# 12VSupply.net
KiCad netlist of a schematic drawn in Altium Designer
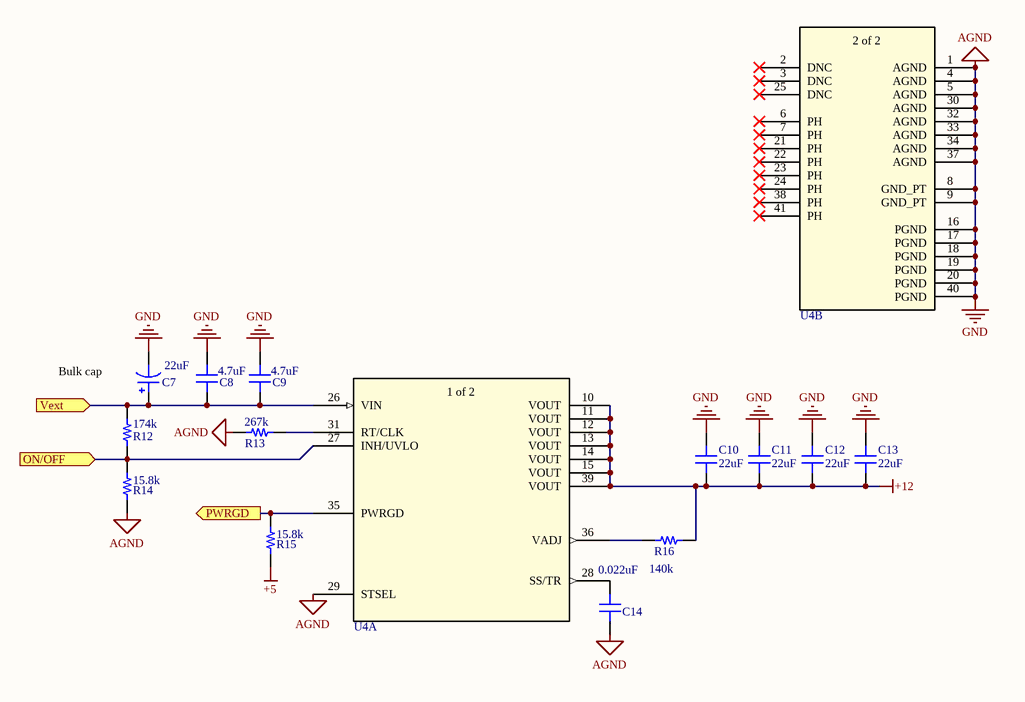
[diagram p0: 12VSupply.SchDoc]

(export (version "E")
  (design (tool "Eeschema 10.0.6"))
  (components
    (comp (ref "C7")
      (value "22uF")
      (footprint "CAP AL TH D8 L3.5 H11.5")
      (description "CAP ALUM 22UF 20% 100V RADIAL")
      (fields
        (field (name "PART NUMBER") "EEU-FC2A220")
        (field (name "MANUFACTURER") "Panasonic Electronic Components")
      )
      (libsource (lib "Celestial Library Database") (part "Polarised Capacitor"))
    )
    (comp (ref "C8")
      (value "4.7uF")
      (footprint "CAP 1206/3216 - 1.0MM")
      (description "CAP CER 4.7UF 50V X5R 1206")
      (fields
        (field (name "PART NUMBER") "C3216X5R1H475K085AB")
        (field (name "MANUFACTURER") "TDK Corporation")
      )
      (libsource (lib "Celestial Library Database") (part "Capacitor"))
    )
    (comp (ref "C9")
      (value "4.7uF")
      (footprint "CAP 1206/3216 - 1.0MM")
      (description "CAP CER 4.7UF 50V X5R 1206")
      (fields
        (field (name "PART NUMBER") "C3216X5R1H475K085AB")
        (field (name "MANUFACTURER") "TDK Corporation")
      )
      (libsource (lib "Celestial Library Database") (part "Capacitor"))
    )
    (comp (ref "C10")
      (value "22uF")
      (footprint "CAP 1206/3216")
      (description "CAP CER 22UF 25V X5R 1206")
      (fields
        (field (name "PART NUMBER") "CL31A226KAHNNNE")
        (field (name "MANUFACTURER") "Samsung Electro-Mechanics America, Inc.")
      )
      (libsource (lib "Celestial Library Database") (part "Capacitor"))
    )
    (comp (ref "C11")
      (value "22uF")
      (footprint "CAP 1206/3216")
      (description "CAP CER 22UF 25V X5R 1206")
      (fields
        (field (name "PART NUMBER") "CL31A226KAHNNNE")
        (field (name "MANUFACTURER") "Samsung Electro-Mechanics America, Inc.")
      )
      (libsource (lib "Celestial Library Database") (part "Capacitor"))
    )
    (comp (ref "C12")
      (value "22uF")
      (footprint "CAP 1206/3216")
      (description "CAP CER 22UF 25V X5R 1206")
      (fields
        (field (name "PART NUMBER") "CL31A226KAHNNNE")
        (field (name "MANUFACTURER") "Samsung Electro-Mechanics America, Inc.")
      )
      (libsource (lib "Celestial Library Database") (part "Capacitor"))
    )
    (comp (ref "C13")
      (value "22uF")
      (footprint "CAP 1206/3216")
      (description "CAP CER 22UF 25V X5R 1206")
      (fields
        (field (name "PART NUMBER") "CL31A226KAHNNNE")
        (field (name "MANUFACTURER") "Samsung Electro-Mechanics America, Inc.")
      )
      (libsource (lib "Celestial Library Database") (part "Capacitor"))
    )
    (comp (ref "C14")
      (value "0.022uF")
      (footprint "CAP 0805/2012")
      (description "CAP CER 0.022UF 100V X7R 0805")
      (fields (field (name "PART NUMBER") "C0805S223K1RAC7800") (field (name "MANUFACTURER") "Kemet"))
      (libsource (lib "Celestial Library Database") (part "Capacitor"))
    )
    (comp (ref "R12")
      (value "174k")
      (footprint "RES 0805/2012")
      (description "RES SMD 174K OHM 1% 1/8W 0805")
      (fields
        (field (name "PART NUMBER") "ERJ-6ENF1743V")
        (field (name "MANUFACTURER") "Panasonic Electronic Components")
      )
      (libsource (lib "Celestial Library Database") (part "Resistor"))
    )
    (comp (ref "R13")
      (value "267k")
      (footprint "RES 1206/3216")
      (description "RES SMD 267K OHM 1% 1/4W 1206")
      (fields
        (field (name "PART NUMBER") "ERJ-8ENF2673V")
        (field (name "MANUFACTURER") "Panasonic Electronic Components")
      )
      (libsource (lib "Celestial Library Database") (part "Resistor"))
    )
    (comp (ref "R14")
      (value "15.8k")
      (footprint "RES 0805/2012")
      (description "RES SMD 15.8K OHM 1% 1/8W 0805")
      (fields
        (field (name "PART NUMBER") "ERJ-6ENF1582V")
        (field (name "MANUFACTURER") "Panasonic Electronic Components")
      )
      (libsource (lib "Celestial Library Database") (part "Resistor"))
    )
    (comp (ref "R15")
      (value "15.8k")
      (footprint "RES 0805/2012")
      (description "RES SMD 15.8K OHM 1% 1/8W 0805")
      (fields
        (field (name "PART NUMBER") "ERJ-6ENF1582V")
        (field (name "MANUFACTURER") "Panasonic Electronic Components")
      )
      (libsource (lib "Celestial Library Database") (part "Resistor"))
    )
    (comp (ref "R16")
      (value "140k")
      (footprint "RES 0805/2012")
      (description "RES SMD 140K OHM 1% 1/8W 0805")
      (fields
        (field (name "PART NUMBER") "ERJ-6ENF1403V")
        (field (name "MANUFACTURER") "Panasonic Electronic Components")
      )
      (libsource (lib "Celestial Library Database") (part "Resistor"))
    )
    (comp (ref "U4")
      (value "LMZ35003RKGR")
      (footprint "RKG41")
      (description "DC DC CONVERTER 2.5-15V 38W")
      (fields
        (field (name "MANUFACTURER_PART_NUMBER") "LMZ34002RKGT")
        (field (name "PART NUMBER") "LMZ34003")
        (field (name "MANUFACTURER") "Texas Instruments")
        (field (name "COPYRIGHT") "Copyright (C) 2018 Accelerated Designs. All rights reserved")
      )
      (libsource (lib "Celestial Library Database") (part "LMZ34003RKGT"))
    )
  )
  (nets
    (net (code "1") (name "+5") (class "Default")
      (node (ref "R15") (pin "1") (pinfunction "1_1") (pintype "passive"))
    )
    (net (code "2") (name "+12") (class "Default")
      (node (ref "C10") (pin "2") (pinfunction "2_2") (pintype "passive"))
      (node (ref "C11") (pin "2") (pinfunction "2_2") (pintype "passive"))
      (node (ref "C12") (pin "2") (pinfunction "2_2") (pintype "passive"))
      (node (ref "C13") (pin "2") (pinfunction "2_2") (pintype "passive"))
      (node (ref "R16") (pin "2") (pinfunction "2_2") (pintype "passive"))
      (node (ref "U4") (pin "10") (pinfunction "VOUT_10") (pintype "power_in"))
      (node (ref "U4") (pin "11") (pinfunction "VOUT_11") (pintype "power_in"))
      (node (ref "U4") (pin "12") (pinfunction "VOUT_12") (pintype "power_in"))
      (node (ref "U4") (pin "13") (pinfunction "VOUT_13") (pintype "power_in"))
      (node (ref "U4") (pin "14") (pinfunction "VOUT_14") (pintype "power_in"))
      (node (ref "U4") (pin "15") (pinfunction "VOUT_15") (pintype "power_in"))
      (node (ref "U4") (pin "39") (pinfunction "VOUT_39") (pintype "power_in"))
    )
    (net (code "3") (name "/ON{slash}OFF") (class "Default")
      (node (ref "R12") (pin "1") (pinfunction "1_1") (pintype "passive"))
      (node (ref "R14") (pin "2") (pinfunction "2_2") (pintype "passive"))
      (node (ref "U4") (pin "27") (pinfunction "INH/UVLO_27") (pintype "passive"))
    )
    (net (code "4") (name "/PWRGD") (class "Default")
      (node (ref "R15") (pin "2") (pinfunction "2_2") (pintype "passive"))
      (node (ref "U4") (pin "35") (pinfunction "PWRGD_35") (pintype "open_emitter"))
    )
    (net (code "5") (name "/Vext") (class "Default")
      (node (ref "C7") (pin "1") (pinfunction "1_1") (pintype "passive"))
      (node (ref "C8") (pin "1") (pinfunction "1_1") (pintype "passive"))
      (node (ref "C9") (pin "1") (pinfunction "1_1") (pintype "passive"))
      (node (ref "R12") (pin "2") (pinfunction "2_2") (pintype "passive"))
      (node (ref "U4") (pin "26") (pinfunction "VIN_26") (pintype "input"))
    )
    (net (code "6") (name "AGND") (class "Default")
      (node (ref "C10") (pin "1") (pinfunction "1_1") (pintype "passive"))
      (node (ref "C11") (pin "1") (pinfunction "1_1") (pintype "passive"))
      (node (ref "C12") (pin "1") (pinfunction "1_1") (pintype "passive"))
      (node (ref "C13") (pin "1") (pinfunction "1_1") (pintype "passive"))
      (node (ref "C14") (pin "1") (pinfunction "1_1") (pintype "passive"))
      (node (ref "C7") (pin "2") (pinfunction "2_2") (pintype "passive"))
      (node (ref "C8") (pin "2") (pinfunction "2_2") (pintype "passive"))
      (node (ref "C9") (pin "2") (pinfunction "2_2") (pintype "passive"))
      (node (ref "R13") (pin "1") (pinfunction "1_1") (pintype "passive"))
      (node (ref "R14") (pin "1") (pinfunction "1_1") (pintype "passive"))
      (node (ref "U4") (pin "1") (pinfunction "AGND_1") (pintype "power_in"))
      (node (ref "U4") (pin "16") (pinfunction "PGND_16") (pintype "power_in"))
      (node (ref "U4") (pin "17") (pinfunction "PGND_17") (pintype "power_in"))
      (node (ref "U4") (pin "18") (pinfunction "PGND_18") (pintype "power_in"))
      (node (ref "U4") (pin "19") (pinfunction "PGND_19") (pintype "power_in"))
      (node (ref "U4") (pin "20") (pinfunction "PGND_20") (pintype "power_in"))
      (node (ref "U4") (pin "29") (pinfunction "STSEL_29") (pintype "passive"))
      (node (ref "U4") (pin "30") (pinfunction "AGND_30") (pintype "power_in"))
      (node (ref "U4") (pin "32") (pinfunction "AGND_32") (pintype "power_in"))
      (node (ref "U4") (pin "33") (pinfunction "AGND_33") (pintype "power_in"))
      (node (ref "U4") (pin "34") (pinfunction "AGND_34") (pintype "power_in"))
      (node (ref "U4") (pin "37") (pinfunction "AGND_37") (pintype "power_in"))
      (node (ref "U4") (pin "4") (pinfunction "AGND_4") (pintype "power_in"))
      (node (ref "U4") (pin "40") (pinfunction "PGND_40") (pintype "power_in"))
      (node (ref "U4") (pin "5") (pinfunction "AGND_5") (pintype "power_in"))
      (node (ref "U4") (pin "8") (pinfunction "GND_PT_8") (pintype "power_in"))
      (node (ref "U4") (pin "9") (pinfunction "GND_PT_9") (pintype "power_in"))
    )
    (net (code "7") (name "Net-(U4A-RT{slash}CLK)") (class "Default")
      (node (ref "R13") (pin "2") (pinfunction "2_2") (pintype "passive"))
      (node (ref "U4") (pin "31") (pinfunction "RT/CLK_31") (pintype "passive"))
    )
    (net (code "8") (name "Net-(U4A-SS{slash}TR)") (class "Default")
      (node (ref "C14") (pin "2") (pinfunction "2_2") (pintype "passive"))
      (node (ref "U4") (pin "28") (pinfunction "SS/TR_28") (pintype "output"))
    )
    (net (code "9") (name "Net-(U4A-VADJ)") (class "Default")
      (node (ref "R16") (pin "1") (pinfunction "1_1") (pintype "passive"))
      (node (ref "U4") (pin "36") (pinfunction "VADJ_36") (pintype "output"))
    )
    (net (code "10") (name "unconnected-(U4B-DNC-Pad2)") (class "Default")
      (node (ref "U4") (pin "2") (pinfunction "DNC_2") (pintype "passive+no_connect"))
    )
    (net (code "11") (name "unconnected-(U4B-DNC-Pad3)") (class "Default")
      (node (ref "U4") (pin "3") (pinfunction "DNC_3") (pintype "passive+no_connect"))
    )
    (net (code "12") (name "unconnected-(U4B-DNC-Pad25)") (class "Default")
      (node (ref "U4") (pin "25") (pinfunction "DNC_25") (pintype "passive+no_connect"))
    )
    (net (code "13") (name "unconnected-(U4B-PH-Pad6)") (class "Default")
      (node (ref "U4") (pin "6") (pinfunction "PH_6") (pintype "passive+no_connect"))
    )
    (net (code "14") (name "unconnected-(U4B-PH-Pad7)") (class "Default")
      (node (ref "U4") (pin "7") (pinfunction "PH_7") (pintype "passive+no_connect"))
    )
    (net (code "15") (name "unconnected-(U4B-PH-Pad21)") (class "Default")
      (node (ref "U4") (pin "21") (pinfunction "PH_21") (pintype "passive+no_connect"))
    )
    (net (code "16") (name "unconnected-(U4B-PH-Pad22)") (class "Default")
      (node (ref "U4") (pin "22") (pinfunction "PH_22") (pintype "passive+no_connect"))
    )
    (net (code "17") (name "unconnected-(U4B-PH-Pad23)") (class "Default")
      (node (ref "U4") (pin "23") (pinfunction "PH_23") (pintype "passive+no_connect"))
    )
    (net (code "18") (name "unconnected-(U4B-PH-Pad24)") (class "Default")
      (node (ref "U4") (pin "24") (pinfunction "PH_24") (pintype "passive+no_connect"))
    )
    (net (code "19") (name "unconnected-(U4B-PH-Pad38)") (class "Default")
      (node (ref "U4") (pin "38") (pinfunction "PH_38") (pintype "passive+no_connect"))
    )
    (net (code "20") (name "unconnected-(U4B-PH-Pad41)") (class "Default")
      (node (ref "U4") (pin "41") (pinfunction "PH_41") (pintype "passive+no_connect"))
    )
  )
)
